# v0_3_1.net
KiCad netlist of a schematic drawn in EAGLE
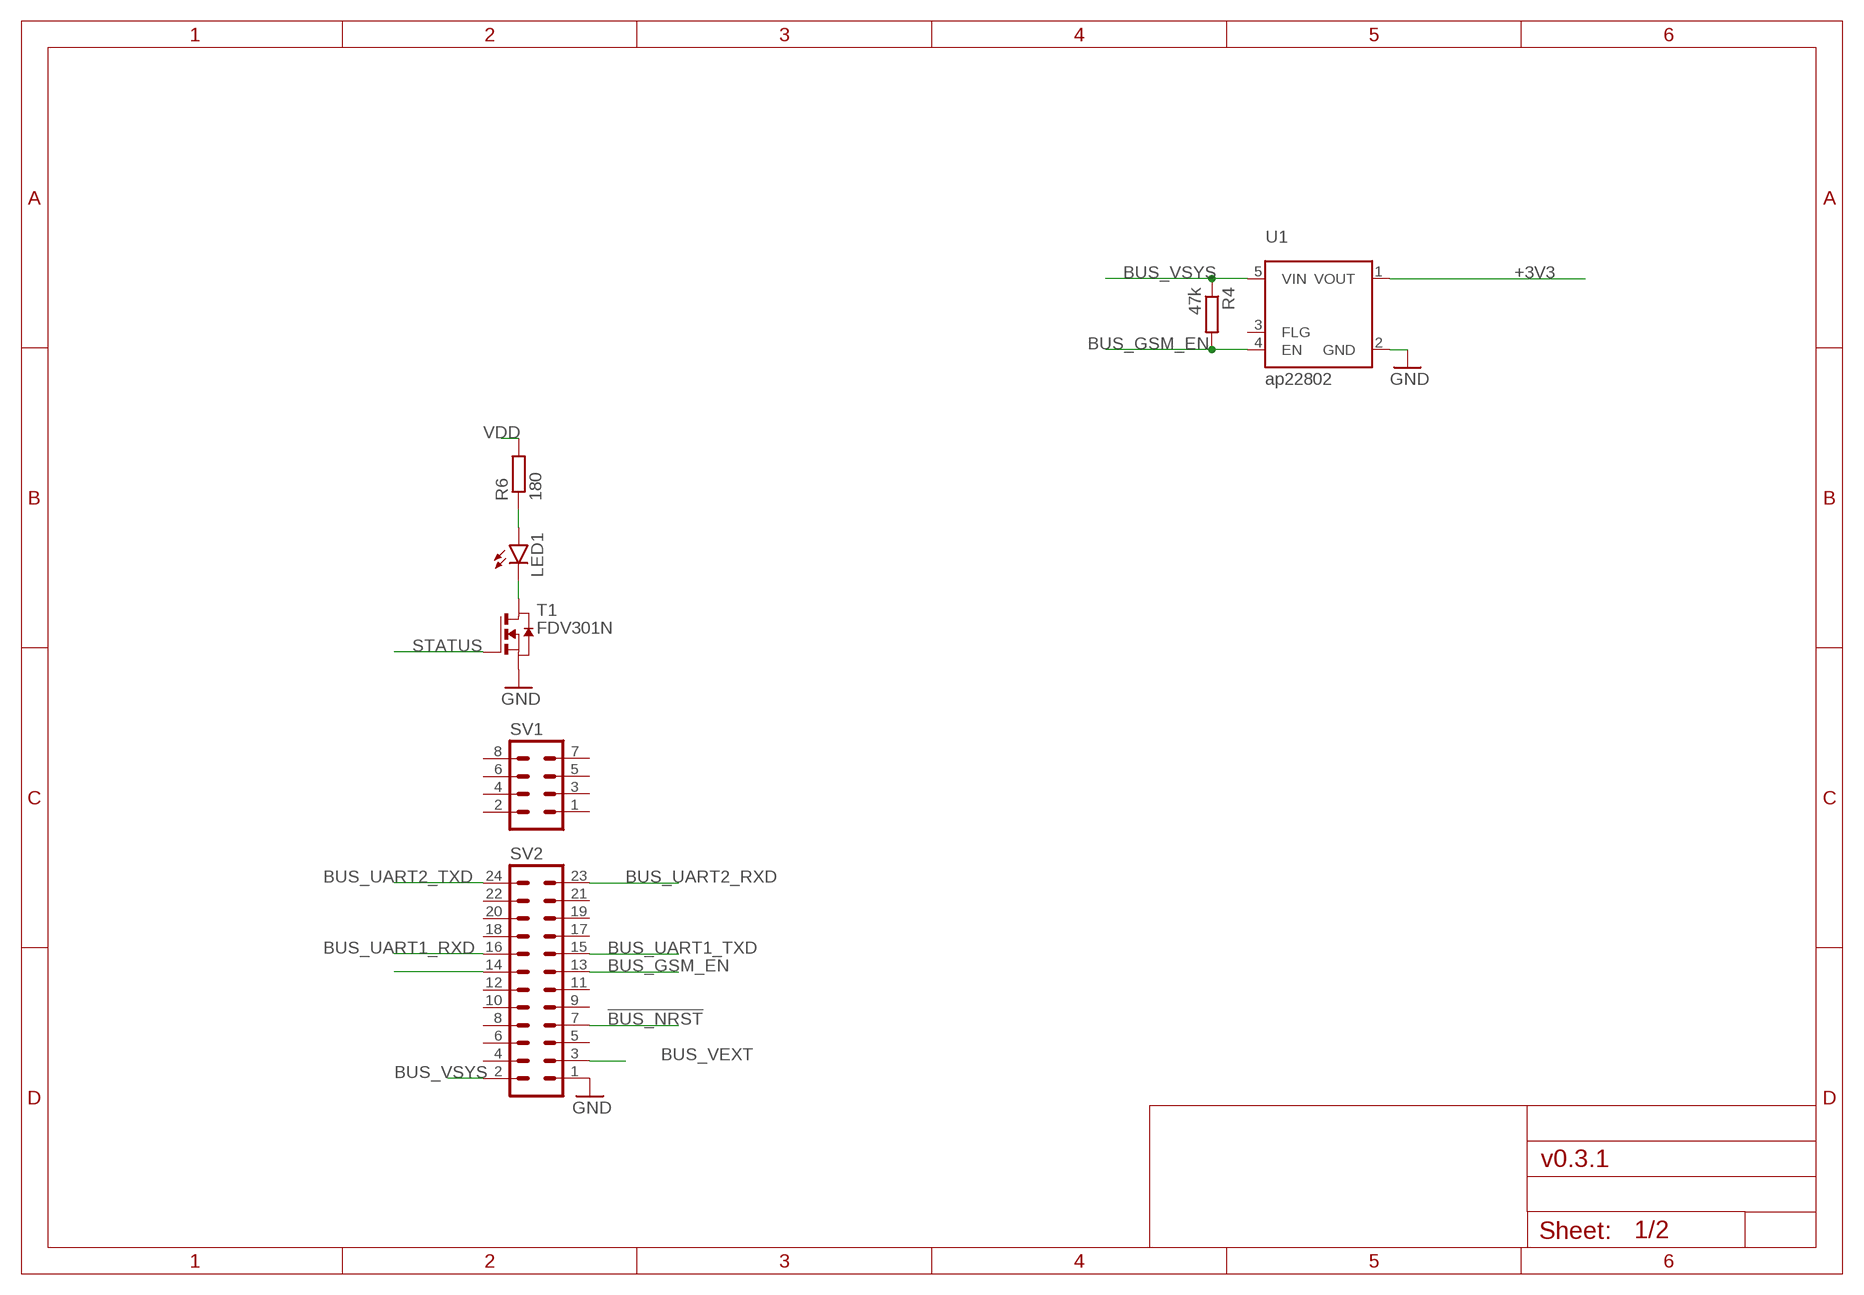
[diagram p0: schematic, sheet 1]
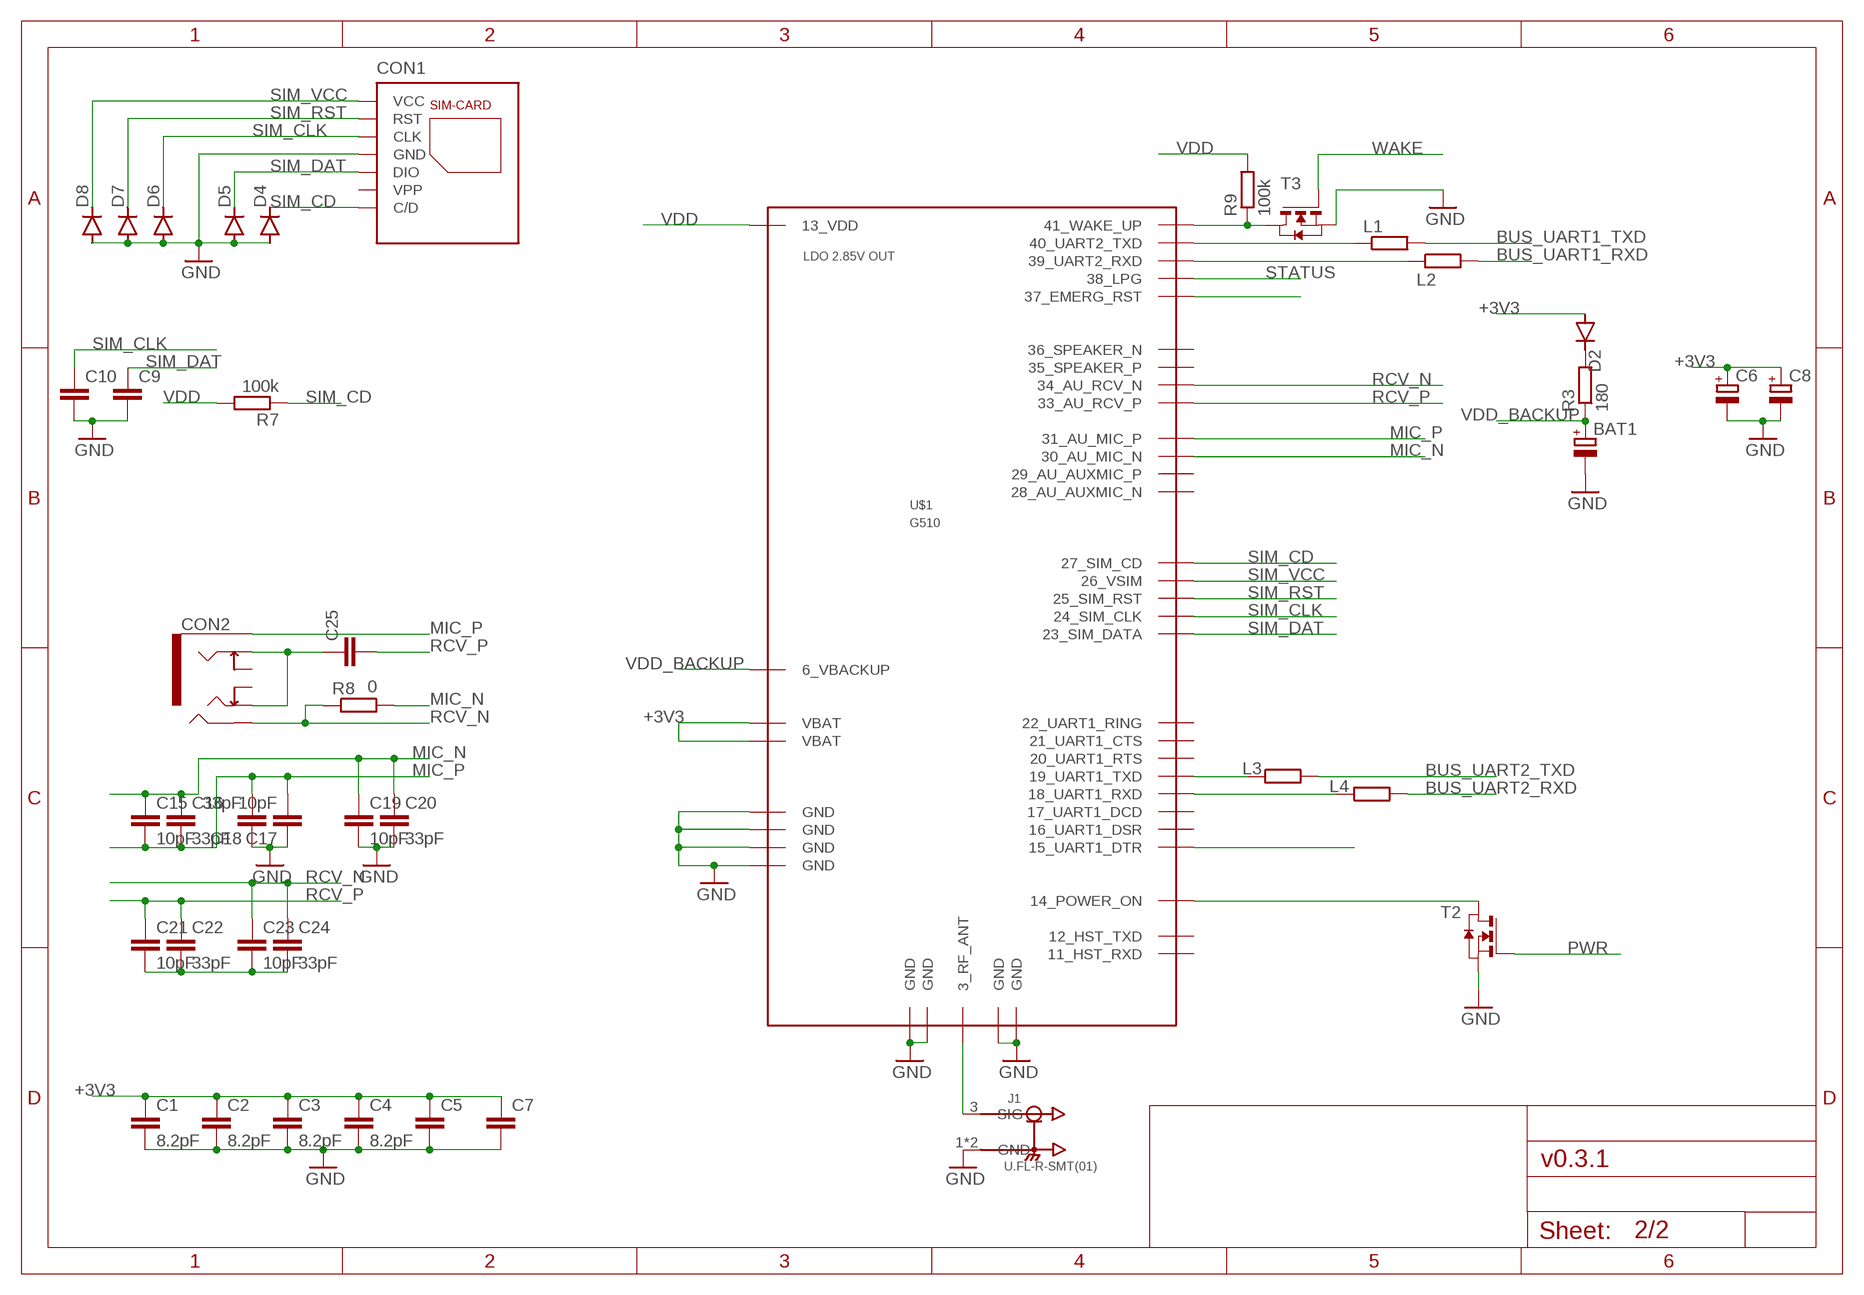
[diagram p1: schematic, sheet 2]

(export (version "E")
  (design (tool "Eeschema 10.0.6"))
  (components
    (comp (ref "LED1")
      (value "LEDCHIP-LED0603")
      (footprint "eagle-import:CHIP-LED0603")
      (libsource (lib "eagle-import") (part "LEDCHIP-LED0603"))
    )
    (comp (ref "R4")
      (value "47k")
      (footprint "eagle-import:R0402")
      (libsource (lib "eagle-import") (part "R-EU_R0402"))
    )
    (comp (ref "R6")
      (value "180")
      (footprint "eagle-import:R0402")
      (libsource (lib "eagle-import") (part "R-EU_R0402"))
    )
    (comp (ref "SV1")
      (value "MA04-2")
      (footprint "eagle-import:MA04-2")
      (libsource (lib "eagle-import") (part "MA04-2"))
    )
    (comp (ref "SV2")
      (value "MA12-2")
      (footprint "eagle-import:MA12-2")
      (libsource (lib "eagle-import") (part "MA12-2"))
    )
    (comp (ref "T1")
      (value "FDV301N")
      (footprint "eagle-import:SOT-23")
      (libsource (lib "eagle-import") (part "NMOSSOT23"))
    )
    (comp (ref "U1")
      (value "ap22802")
      (footprint "eagle-import:SOT25")
      (libsource (lib "eagle-import") (part "AP22802"))
    )
    (comp (ref "BAT1")
      (value "DCK-3R3E224U-E")
      (footprint "eagle-import:621")
      (libsource (lib "eagle-import") (part "DCK-3R3E224U-E"))
    )
    (comp (ref "C1")
      (value "8.2pF")
      (footprint "eagle-import:C0402")
      (libsource (lib "eagle-import") (part "C-EUC0402"))
    )
    (comp (ref "C2")
      (value "8.2pF")
      (footprint "eagle-import:C0402")
      (libsource (lib "eagle-import") (part "C-EUC0402"))
    )
    (comp (ref "C3")
      (value "8.2pF")
      (footprint "eagle-import:C0402")
      (libsource (lib "eagle-import") (part "C-EUC0402"))
    )
    (comp (ref "C4")
      (value "8.2pF")
      (footprint "eagle-import:C0402")
      (libsource (lib "eagle-import") (part "C-EUC0402"))
    )
    (comp (ref "C5")
      (value "C-EUC0603")
      (footprint "eagle-import:C0603")
      (libsource (lib "eagle-import") (part "C-EUC0603"))
    )
    (comp (ref "C6")
      (value "CPOL-EUSMCC")
      (footprint "eagle-import:SMC_C")
      (libsource (lib "eagle-import") (part "CPOL-EUSMCC"))
    )
    (comp (ref "C7")
      (value "C-EUC0603")
      (footprint "eagle-import:C0603")
      (libsource (lib "eagle-import") (part "C-EUC0603"))
    )
    (comp (ref "C8")
      (value "CPOL-EUSMCC")
      (footprint "eagle-import:SMC_C")
      (libsource (lib "eagle-import") (part "CPOL-EUSMCC"))
    )
    (comp (ref "C9")
      (value "C-EUC0402")
      (footprint "eagle-import:C0402")
      (libsource (lib "eagle-import") (part "C-EUC0402"))
    )
    (comp (ref "C10")
      (value "C-EUC0402")
      (footprint "eagle-import:C0402")
      (libsource (lib "eagle-import") (part "C-EUC0402"))
    )
    (comp (ref "C15")
      (value "10pF")
      (footprint "eagle-import:C0402")
      (libsource (lib "eagle-import") (part "C-EUC0402"))
    )
    (comp (ref "C16")
      (value "33pF")
      (footprint "eagle-import:C0402")
      (libsource (lib "eagle-import") (part "C-EUC0402"))
    )
    (comp (ref "C17")
      (value "10pF")
      (footprint "eagle-import:C0402")
      (libsource (lib "eagle-import") (part "C-EUC0402"))
    )
    (comp (ref "C18")
      (value "33pF")
      (footprint "eagle-import:C0402")
      (libsource (lib "eagle-import") (part "C-EUC0402"))
    )
    (comp (ref "C19")
      (value "10pF")
      (footprint "eagle-import:C0402")
      (libsource (lib "eagle-import") (part "C-EUC0402"))
    )
    (comp (ref "C20")
      (value "33pF")
      (footprint "eagle-import:C0402")
      (libsource (lib "eagle-import") (part "C-EUC0402"))
    )
    (comp (ref "C21")
      (value "10pF")
      (footprint "eagle-import:C0402")
      (libsource (lib "eagle-import") (part "C-EUC0402"))
    )
    (comp (ref "C22")
      (value "33pF")
      (footprint "eagle-import:C0402")
      (libsource (lib "eagle-import") (part "C-EUC0402"))
    )
    (comp (ref "C23")
      (value "10pF")
      (footprint "eagle-import:C0402")
      (libsource (lib "eagle-import") (part "C-EUC0402"))
    )
    (comp (ref "C24")
      (value "33pF")
      (footprint "eagle-import:C0402")
      (libsource (lib "eagle-import") (part "C-EUC0402"))
    )
    (comp (ref "C25")
      (value "C-EUC0603")
      (footprint "eagle-import:C0603")
      (libsource (lib "eagle-import") (part "C-EUC0603"))
    )
    (comp (ref "CON1")
      (value "115Q-BCA0")
      (footprint "eagle-import:115Q")
      (libsource (lib "eagle-import") (part "115Q-BCA0"))
    )
    (comp (ref "CON2")
      (value "1503-21")
      (footprint "eagle-import:150321")
      (libsource (lib "eagle-import") (part "1503-21"))
    )
    (comp (ref "D2")
      (value "DIODE-SOD323-R")
      (footprint "eagle-import:SOD323-R")
      (libsource (lib "eagle-import") (part "DIODE-SOD323-R"))
    )
    (comp (ref "D4")
      (value "DIODE-SOD323-R")
      (footprint "eagle-import:SOD323-R")
      (libsource (lib "eagle-import") (part "DIODE-SOD323-R"))
    )
    (comp (ref "D5")
      (value "DIODE-SOD323-R")
      (footprint "eagle-import:SOD323-R")
      (libsource (lib "eagle-import") (part "DIODE-SOD323-R"))
    )
    (comp (ref "D6")
      (value "DIODE-SOD323-R")
      (footprint "eagle-import:SOD323-R")
      (libsource (lib "eagle-import") (part "DIODE-SOD323-R"))
    )
    (comp (ref "D7")
      (value "DIODE-SOD323-R")
      (footprint "eagle-import:SOD323-R")
      (libsource (lib "eagle-import") (part "DIODE-SOD323-R"))
    )
    (comp (ref "D8")
      (value "DIODE-SOD323-R")
      (footprint "eagle-import:SOD323-R")
      (libsource (lib "eagle-import") (part "DIODE-SOD323-R"))
    )
    (comp (ref "J1")
      (value "U.FL-R-SMT(01)")
      (footprint "eagle-import:HRS_U.FL-R-SMT(01)")
      (fields (field (name "MF") "Hirose") (field (name "MP") "U.FL-R-SMT_01_"))
      (libsource (lib "eagle-import") (part "U.FL-R-SMT(01)"))
    )
    (comp (ref "L1")
      (value "R-EU_R0402")
      (footprint "eagle-import:R0402")
      (libsource (lib "eagle-import") (part "R-EU_R0402"))
    )
    (comp (ref "L2")
      (value "R-EU_R0402")
      (footprint "eagle-import:R0402")
      (libsource (lib "eagle-import") (part "R-EU_R0402"))
    )
    (comp (ref "L3")
      (value "R-EU_R0402")
      (footprint "eagle-import:R0402")
      (libsource (lib "eagle-import") (part "R-EU_R0402"))
    )
    (comp (ref "L4")
      (value "R-EU_R0402")
      (footprint "eagle-import:R0402")
      (libsource (lib "eagle-import") (part "R-EU_R0402"))
    )
    (comp (ref "R3")
      (value "180")
      (footprint "eagle-import:R0402")
      (libsource (lib "eagle-import") (part "R-EU_R0402"))
    )
    (comp (ref "R7")
      (value "100k")
      (footprint "eagle-import:R0402")
      (libsource (lib "eagle-import") (part "R-EU_R0402"))
    )
    (comp (ref "R8")
      (value "0")
      (footprint "eagle-import:R0402")
      (libsource (lib "eagle-import") (part "R-EU_R0402"))
    )
    (comp (ref "R9")
      (value "100k")
      (footprint "eagle-import:R0402")
      (libsource (lib "eagle-import") (part "R-EU_R0402"))
    )
    (comp (ref "T2")
      (value "NMOSSOT23")
      (footprint "eagle-import:SOT-23")
      (libsource (lib "eagle-import") (part "NMOSSOT23"))
    )
    (comp (ref "T3")
      (value "NMOSSOT23")
      (footprint "eagle-import:SOT-23")
      (libsource (lib "eagle-import") (part "NMOSSOT23"))
    )
    (comp (ref "U$1")
      (value "G510")
      (footprint "eagle-import:G510")
      (libsource (lib "eagle-import") (part "G510"))
    )
  )
  (nets
    (net (code "1") (name "+3V3") (class "Default")
      (node (ref "C1") (pin "1") (pinfunction "1_1") (pintype "passive"))
      (node (ref "C2") (pin "1") (pinfunction "1_1") (pintype "passive"))
      (node (ref "C3") (pin "1") (pinfunction "1_1") (pintype "passive"))
      (node (ref "C4") (pin "1") (pinfunction "1_1") (pintype "passive"))
      (node (ref "C5") (pin "1") (pinfunction "1_1") (pintype "passive"))
      (node (ref "C6") (pin "+") (pinfunction "+_+") (pintype "passive"))
      (node (ref "C7") (pin "1") (pinfunction "1_1") (pintype "passive"))
      (node (ref "C8") (pin "+") (pinfunction "+_+") (pintype "passive"))
      (node (ref "D2") (pin "A") (pinfunction "A_A") (pintype "passive"))
      (node (ref "U$1") (pin "10_VBAT") (pinfunction "VBAT_10_VBAT") (pintype "power_in"))
      (node (ref "U$1") (pin "9_VBAT") (pinfunction "VBAT_9_VBAT") (pintype "power_in"))
      (node (ref "U1") (pin "1") (pinfunction "VOUT_1") (pintype "bidirectional"))
    )
    (net (code "2") (name "BUS_GSM_EN") (class "Default")
      (node (ref "R4") (pin "2") (pinfunction "2_2") (pintype "passive"))
      (node (ref "SV2") (pin "13") (pinfunction "13_13") (pintype "passive"))
      (node (ref "U1") (pin "4") (pinfunction "EN_4") (pintype "bidirectional"))
    )
    (net (code "3") (name "BUS_UART1_RXD") (class "Default")
      (node (ref "L2") (pin "2") (pinfunction "2_2") (pintype "passive"))
      (node (ref "SV2") (pin "16") (pinfunction "16_16") (pintype "passive"))
    )
    (net (code "4") (name "BUS_UART1_TXD") (class "Default")
      (node (ref "L1") (pin "2") (pinfunction "2_2") (pintype "passive"))
      (node (ref "SV2") (pin "15") (pinfunction "15_15") (pintype "passive"))
    )
    (net (code "5") (name "BUS_UART2_RXD") (class "Default")
      (node (ref "L4") (pin "2") (pinfunction "2_2") (pintype "passive"))
      (node (ref "SV2") (pin "23") (pinfunction "23_23") (pintype "passive"))
    )
    (net (code "6") (name "BUS_UART2_TXD") (class "Default")
      (node (ref "L3") (pin "2") (pinfunction "2_2") (pintype "passive"))
      (node (ref "SV2") (pin "24") (pinfunction "24_24") (pintype "passive"))
    )
    (net (code "7") (name "BUS_VEXT") (class "Default")
      (node (ref "SV2") (pin "3") (pinfunction "3_3") (pintype "passive"))
    )
    (net (code "8") (name "BUS_VSYS") (class "Default")
      (node (ref "R4") (pin "1") (pinfunction "1_1") (pintype "passive"))
      (node (ref "SV2") (pin "2") (pinfunction "2_2") (pintype "passive"))
      (node (ref "U1") (pin "5") (pinfunction "VIN_5") (pintype "bidirectional"))
    )
    (net (code "9") (name "GND") (class "Default")
      (node (ref "BAT1") (pin "-") (pinfunction "-_-") (pintype "passive"))
      (node (ref "C1") (pin "2") (pinfunction "2_2") (pintype "passive"))
      (node (ref "C10") (pin "2") (pinfunction "2_2") (pintype "passive"))
      (node (ref "C17") (pin "1") (pinfunction "1_1") (pintype "passive"))
      (node (ref "C18") (pin "1") (pinfunction "1_1") (pintype "passive"))
      (node (ref "C19") (pin "2") (pinfunction "2_2") (pintype "passive"))
      (node (ref "C2") (pin "2") (pinfunction "2_2") (pintype "passive"))
      (node (ref "C20") (pin "2") (pinfunction "2_2") (pintype "passive"))
      (node (ref "C3") (pin "2") (pinfunction "2_2") (pintype "passive"))
      (node (ref "C4") (pin "2") (pinfunction "2_2") (pintype "passive"))
      (node (ref "C5") (pin "2") (pinfunction "2_2") (pintype "passive"))
      (node (ref "C6") (pin "-") (pinfunction "-_-") (pintype "passive"))
      (node (ref "C7") (pin "2") (pinfunction "2_2") (pintype "passive"))
      (node (ref "C8") (pin "-") (pinfunction "-_-") (pintype "passive"))
      (node (ref "C9") (pin "2") (pinfunction "2_2") (pintype "passive"))
      (node (ref "CON1") (pin "GND1") (pinfunction "GND_GND1") (pintype "passive"))
      (node (ref "CON1") (pin "GND2") (pinfunction "GND_GND2") (pintype "passive"))
      (node (ref "CON1") (pin "GND3") (pinfunction "GND_GND3") (pintype "passive"))
      (node (ref "CON1") (pin "GND4") (pinfunction "GND_GND4") (pintype "passive"))
      (node (ref "CON1") (pin "P5") (pinfunction "GND_P5") (pintype "passive"))
      (node (ref "D4") (pin "A") (pinfunction "A_A") (pintype "passive"))
      (node (ref "D5") (pin "A") (pinfunction "A_A") (pintype "passive"))
      (node (ref "D6") (pin "A") (pinfunction "A_A") (pintype "passive"))
      (node (ref "D7") (pin "A") (pinfunction "A_A") (pintype "passive"))
      (node (ref "D8") (pin "A") (pinfunction "A_A") (pintype "passive"))
      (node (ref "J1") (pin "1") (pinfunction "GND_1") (pintype "passive"))
      (node (ref "J1") (pin "2") (pinfunction "GND_2") (pintype "passive"))
      (node (ref "SV2") (pin "1") (pinfunction "1_1") (pintype "passive"))
      (node (ref "T1") (pin "2") (pinfunction "S_2") (pintype "passive"))
      (node (ref "T2") (pin "2") (pinfunction "S_2") (pintype "passive"))
      (node (ref "T3") (pin "2") (pinfunction "S_2") (pintype "passive"))
      (node (ref "U$1") (pin "1_GND") (pinfunction "GND_1_GND") (pintype "power_in"))
      (node (ref "U$1") (pin "2_GND") (pinfunction "GND_2_GND") (pintype "power_in"))
      (node (ref "U$1") (pin "32_GND") (pinfunction "GND_32_GND") (pintype "power_in"))
      (node (ref "U$1") (pin "42_GND") (pinfunction "GND_42_GND") (pintype "power_in"))
      (node (ref "U$1") (pin "4_GND") (pinfunction "GND_4_GND") (pintype "power_in"))
      (node (ref "U$1") (pin "5_GND") (pinfunction "GND_5_GND") (pintype "power_in"))
      (node (ref "U$1") (pin "7_GND") (pinfunction "GND_7_GND") (pintype "power_in"))
      (node (ref "U$1") (pin "8_GND") (pinfunction "GND_8_GND") (pintype "power_in"))
      (node (ref "U1") (pin "2") (pinfunction "GND_2") (pintype "bidirectional"))
    )
    (net (code "10") (name "MIC_N") (class "Default")
      (node (ref "C15") (pin "1") (pinfunction "1_1") (pintype "passive"))
      (node (ref "C16") (pin "1") (pinfunction "1_1") (pintype "passive"))
      (node (ref "C19") (pin "1") (pinfunction "1_1") (pintype "passive"))
      (node (ref "C20") (pin "1") (pinfunction "1_1") (pintype "passive"))
      (node (ref "R8") (pin "2") (pinfunction "2_2") (pintype "passive"))
      (node (ref "U$1") (pin "30_AU_MIC_N") (pinfunction "30_AU_MIC_N_30_AU_MIC_N") (pintype "bidirectional"))
    )
    (net (code "11") (name "MIC_P") (class "Default")
      (node (ref "C15") (pin "2") (pinfunction "2_2") (pintype "passive"))
      (node (ref "C16") (pin "2") (pinfunction "2_2") (pintype "passive"))
      (node (ref "C17") (pin "2") (pinfunction "2_2") (pintype "passive"))
      (node (ref "C18") (pin "2") (pinfunction "2_2") (pintype "passive"))
      (node (ref "CON2") (pin "1") (pinfunction "1_1") (pintype "bidirectional"))
      (node (ref "U$1") (pin "31_AU_MIC_P") (pinfunction "31_AU_MIC_P_31_AU_MIC_P") (pintype "bidirectional"))
    )
    (net (code "12") (name "Net-(C21-Pad2)") (class "Default")
      (node (ref "C21") (pin "2") (pinfunction "2_2") (pintype "passive"))
      (node (ref "C22") (pin "2") (pinfunction "2_2") (pintype "passive"))
      (node (ref "C23") (pin "2") (pinfunction "2_2") (pintype "passive"))
      (node (ref "C24") (pin "2") (pinfunction "2_2") (pintype "passive"))
    )
    (net (code "13") (name "Net-(C25-Pad1)") (class "Default")
      (node (ref "C25") (pin "1") (pinfunction "1_1") (pintype "passive"))
      (node (ref "CON2") (pin "3") (pinfunction "3_3") (pintype "bidirectional"))
      (node (ref "CON2") (pin "5") (pinfunction "5_5") (pintype "bidirectional"))
    )
    (net (code "14") (name "Net-(D2-PadC)") (class "Default")
      (node (ref "D2") (pin "C") (pinfunction "C_C") (pintype "passive"))
      (node (ref "R3") (pin "2") (pinfunction "2_2") (pintype "passive"))
    )
    (net (code "15") (name "Net-(J1-SIG)") (class "Default")
      (node (ref "J1") (pin "3") (pinfunction "SIG_3") (pintype "passive"))
      (node (ref "U$1") (pin "3_RF_ANT") (pinfunction "3_RF_ANT_3_RF_ANT") (pintype "bidirectional"))
    )
    (net (code "16") (name "Net-(L1-Pad1)") (class "Default")
      (node (ref "L1") (pin "1") (pinfunction "1_1") (pintype "passive"))
      (node (ref "U$1") (pin "40_UART2_TXD") (pinfunction "40_UART2_TXD_40_UART2_TXD") (pintype "output"))
    )
    (net (code "17") (name "Net-(L2-Pad1)") (class "Default")
      (node (ref "L2") (pin "1") (pinfunction "1_1") (pintype "passive"))
      (node (ref "U$1") (pin "39_UART2_RXD") (pinfunction "39_UART2_RXD_39_UART2_RXD") (pintype "input"))
    )
    (net (code "18") (name "Net-(L3-Pad1)") (class "Default")
      (node (ref "L3") (pin "1") (pinfunction "1_1") (pintype "passive"))
      (node (ref "U$1") (pin "19_UART1_TXD") (pinfunction "19_UART1_TXD_19_UART1_TXD") (pintype "output"))
    )
    (net (code "19") (name "Net-(L4-Pad1)") (class "Default")
      (node (ref "L4") (pin "1") (pinfunction "1_1") (pintype "passive"))
      (node (ref "U$1") (pin "18_UART1_RXD") (pinfunction "18_UART1_RXD_18_UART1_RXD") (pintype "input"))
    )
    (net (code "20") (name "Net-(LED1-PadA)") (class "Default")
      (node (ref "LED1") (pin "A") (pinfunction "A_A") (pintype "passive"))
      (node (ref "R6") (pin "1") (pinfunction "1_1") (pintype "passive"))
    )
    (net (code "21") (name "Net-(T1-D)") (class "Default")
      (node (ref "LED1") (pin "C") (pinfunction "C_C") (pintype "passive"))
      (node (ref "T1") (pin "1") (pinfunction "D_1") (pintype "passive"))
    )
    (net (code "22") (name "Net-(T2-D)") (class "Default")
      (node (ref "T2") (pin "1") (pinfunction "D_1") (pintype "passive"))
      (node (ref "U$1") (pin "14_POWER_ON") (pinfunction "14_POWER_ON_14_POWER_ON") (pintype "input"))
    )
    (net (code "23") (name "Net-(T3-D)") (class "Default")
      (node (ref "R9") (pin "1") (pinfunction "1_1") (pintype "passive"))
      (node (ref "T3") (pin "1") (pinfunction "D_1") (pintype "passive"))
      (node (ref "U$1") (pin "41_WAKE_UP") (pinfunction "41_WAKE_UP_41_WAKE_UP") (pintype "bidirectional"))
    )
    (net (code "24") (name "PWR") (class "Default")
      (node (ref "T2") (pin "3") (pinfunction "G_3") (pintype "passive"))
    )
    (net (code "25") (name "RCV_N") (class "Default")
      (node (ref "C23") (pin "1") (pinfunction "1_1") (pintype "passive"))
      (node (ref "C24") (pin "1") (pinfunction "1_1") (pintype "passive"))
      (node (ref "CON2") (pin "2") (pinfunction "2_2") (pintype "bidirectional"))
      (node (ref "R8") (pin "1") (pinfunction "1_1") (pintype "passive"))
      (node (ref "U$1") (pin "34_AU_RCV_N") (pinfunction "34_AU_RCV_N_34_AU_RCV_N") (pintype "bidirectional"))
    )
    (net (code "26") (name "RCV_P") (class "Default")
      (node (ref "C21") (pin "1") (pinfunction "1_1") (pintype "passive"))
      (node (ref "C22") (pin "1") (pinfunction "1_1") (pintype "passive"))
      (node (ref "C25") (pin "2") (pinfunction "2_2") (pintype "passive"))
      (node (ref "U$1") (pin "33_AU_RCV_P") (pinfunction "33_AU_RCV_P_33_AU_RCV_P") (pintype "bidirectional"))
    )
    (net (code "27") (name "SIM_CD") (class "Default")
      (node (ref "CON1") (pin "CD") (pinfunction "C/D_CD") (pintype "passive"))
      (node (ref "D4") (pin "C") (pinfunction "C_C") (pintype "passive"))
      (node (ref "R7") (pin "1") (pinfunction "1_1") (pintype "passive"))
      (node (ref "U$1") (pin "27_SIM_CD") (pinfunction "27_SIM_CD_27_SIM_CD") (pintype "bidirectional"))
    )
    (net (code "28") (name "SIM_CLK") (class "Default")
      (node (ref "C10") (pin "1") (pinfunction "1_1") (pintype "passive"))
      (node (ref "CON1") (pin "P3") (pinfunction "CLK_P3") (pintype "passive"))
      (node (ref "D6") (pin "C") (pinfunction "C_C") (pintype "passive"))
      (node (ref "U$1") (pin "24_SIM_CLK") (pinfunction "24_SIM_CLK_24_SIM_CLK") (pintype "bidirectional"))
    )
    (net (code "29") (name "SIM_DAT") (class "Default")
      (node (ref "C9") (pin "1") (pinfunction "1_1") (pintype "passive"))
      (node (ref "CON1") (pin "P7") (pinfunction "DIO_P7") (pintype "passive"))
      (node (ref "D5") (pin "C") (pinfunction "C_C") (pintype "passive"))
      (node (ref "U$1") (pin "23_SIM_DATA") (pinfunction "23_SIM_DATA_23_SIM_DATA") (pintype "bidirectional"))
    )
    (net (code "30") (name "SIM_RST") (class "Default")
      (node (ref "CON1") (pin "P2") (pinfunction "RST_P2") (pintype "passive"))
      (node (ref "D7") (pin "C") (pinfunction "C_C") (pintype "passive"))
      (node (ref "U$1") (pin "25_SIM_RST") (pinfunction "25_SIM_RST_25_SIM_RST") (pintype "bidirectional"))
    )
    (net (code "31") (name "SIM_VCC") (class "Default")
      (node (ref "CON1") (pin "P1") (pinfunction "VCC_P1") (pintype "passive"))
      (node (ref "D8") (pin "C") (pinfunction "C_C") (pintype "passive"))
      (node (ref "U$1") (pin "26_VSIM") (pinfunction "26_VSIM_26_VSIM") (pintype "bidirectional"))
    )
    (net (code "32") (name "STATUS") (class "Default")
      (node (ref "T1") (pin "3") (pinfunction "G_3") (pintype "passive"))
      (node (ref "U$1") (pin "38_LPG") (pinfunction "38_LPG_38_LPG") (pintype "output"))
    )
    (net (code "33") (name "VDD") (class "Default")
      (node (ref "R6") (pin "2") (pinfunction "2_2") (pintype "passive"))
      (node (ref "R7") (pin "2") (pinfunction "2_2") (pintype "passive"))
      (node (ref "R9") (pin "2") (pinfunction "2_2") (pintype "passive"))
      (node (ref "U$1") (pin "13_VDD") (pinfunction "13_VDD_13_VDD") (pintype "power_in"))
    )
    (net (code "34") (name "VDD_BACKUP") (class "Default")
      (node (ref "BAT1") (pin "+") (pinfunction "+_+") (pintype "passive"))
      (node (ref "R3") (pin "1") (pinfunction "1_1") (pintype "passive"))
      (node (ref "U$1") (pin "6_VBACKUP") (pinfunction "6_VBACKUP_6_VBACKUP") (pintype "power_in"))
    )
    (net (code "35") (name "WAKE") (class "Default")
      (node (ref "T3") (pin "3") (pinfunction "G_3") (pintype "passive"))
    )
    (net (code "36") (name "unconnected-(CON1-VPP-PadP6)") (class "Default")
      (node (ref "CON1") (pin "P6") (pinfunction "VPP_P6") (pintype "passive"))
    )
    (net (code "37") (name "unconnected-(CON2-Pad4)") (class "Default")
      (node (ref "CON2") (pin "4") (pinfunction "4_4") (pintype "bidirectional"))
    )
    (net (code "38") (name "unconnected-(CON2-Pad6)") (class "Default")
      (node (ref "CON2") (pin "6") (pinfunction "6_6") (pintype "bidirectional"))
    )
    (net (code "39") (name "unconnected-(SV1-Pad1)") (class "Default")
      (node (ref "SV1") (pin "1") (pinfunction "1_1") (pintype "passive"))
    )
    (net (code "40") (name "unconnected-(SV1-Pad2)") (class "Default")
      (node (ref "SV1") (pin "2") (pinfunction "2_2") (pintype "passive"))
    )
    (net (code "41") (name "unconnected-(SV1-Pad3)") (class "Default")
      (node (ref "SV1") (pin "3") (pinfunction "3_3") (pintype "passive"))
    )
    (net (code "42") (name "unconnected-(SV1-Pad4)") (class "Default")
      (node (ref "SV1") (pin "4") (pinfunction "4_4") (pintype "passive"))
    )
    (net (code "43") (name "unconnected-(SV1-Pad5)") (class "Default")
      (node (ref "SV1") (pin "5") (pinfunction "5_5") (pintype "passive"))
    )
    (net (code "44") (name "unconnected-(SV1-Pad6)") (class "Default")
      (node (ref "SV1") (pin "6") (pinfunction "6_6") (pintype "passive"))
    )
    (net (code "45") (name "unconnected-(SV1-Pad7)") (class "Default")
      (node (ref "SV1") (pin "7") (pinfunction "7_7") (pintype "passive"))
    )
    (net (code "46") (name "unconnected-(SV1-Pad8)") (class "Default")
      (node (ref "SV1") (pin "8") (pinfunction "8_8") (pintype "passive"))
    )
    (net (code "47") (name "unconnected-(SV2-Pad4)") (class "Default")
      (node (ref "SV2") (pin "4") (pinfunction "4_4") (pintype "passive"))
    )
    (net (code "48") (name "unconnected-(SV2-Pad5)") (class "Default")
      (node (ref "SV2") (pin "5") (pinfunction "5_5") (pintype "passive"))
    )
    (net (code "49") (name "unconnected-(SV2-Pad6)") (class "Default")
      (node (ref "SV2") (pin "6") (pinfunction "6_6") (pintype "passive"))
    )
    (net (code "50") (name "unconnected-(SV2-Pad8)") (class "Default")
      (node (ref "SV2") (pin "8") (pinfunction "8_8") (pintype "passive"))
    )
    (net (code "51") (name "unconnected-(SV2-Pad9)") (class "Default")
      (node (ref "SV2") (pin "9") (pinfunction "9_9") (pintype "passive"))
    )
    (net (code "52") (name "unconnected-(SV2-Pad10)") (class "Default")
      (node (ref "SV2") (pin "10") (pinfunction "10_10") (pintype "passive"))
    )
    (net (code "53") (name "unconnected-(SV2-Pad11)") (class "Default")
      (node (ref "SV2") (pin "11") (pinfunction "11_11") (pintype "passive"))
    )
    (net (code "54") (name "unconnected-(SV2-Pad12)") (class "Default")
      (node (ref "SV2") (pin "12") (pinfunction "12_12") (pintype "passive"))
    )
    (net (code "55") (name "unconnected-(SV2-Pad14)") (class "Default")
      (node (ref "SV2") (pin "14") (pinfunction "14_14") (pintype "passive"))
    )
    (net (code "56") (name "unconnected-(SV2-Pad17)") (class "Default")
      (node (ref "SV2") (pin "17") (pinfunction "17_17") (pintype "passive"))
    )
    (net (code "57") (name "unconnected-(SV2-Pad18)") (class "Default")
      (node (ref "SV2") (pin "18") (pinfunction "18_18") (pintype "passive"))
    )
    (net (code "58") (name "unconnected-(SV2-Pad19)") (class "Default")
      (node (ref "SV2") (pin "19") (pinfunction "19_19") (pintype "passive"))
    )
    (net (code "59") (name "unconnected-(SV2-Pad20)") (class "Default")
      (node (ref "SV2") (pin "20") (pinfunction "20_20") (pintype "passive"))
    )
    (net (code "60") (name "unconnected-(SV2-Pad21)") (class "Default")
      (node (ref "SV2") (pin "21") (pinfunction "21_21") (pintype "passive"))
    )
    (net (code "61") (name "unconnected-(SV2-Pad22)") (class "Default")
      (node (ref "SV2") (pin "22") (pinfunction "22_22") (pintype "passive"))
    )
    (net (code "62") (name "unconnected-(U$1-11_HST_RXD-Pad11_HSTRXD)") (class "Default")
      (node (ref "U$1") (pin "11_HSTRXD") (pinfunction "11_HST_RXD_11_HSTRXD") (pintype "input"))
    )
    (net (code "63") (name "unconnected-(U$1-Pad12_HST_TXD)") (class "Default")
      (node (ref "U$1") (pin "12_HST_TXD") (pinfunction "12_HST_TXD_12_HST_TXD") (pintype "output"))
    )
    (net (code "64") (name "unconnected-(U$1-Pad15_UART1_DTR)") (class "Default")
      (node (ref "U$1") (pin "15_UART1_DTR") (pinfunction "15_UART1_DTR_15_UART1_DTR") (pintype "bidirectional"))
    )
    (net (code "65") (name "unconnected-(U$1-Pad16_UART1_DSR)") (class "Default")
      (node (ref "U$1") (pin "16_UART1_DSR") (pinfunction "16_UART1_DSR_16_UART1_DSR") (pintype "bidirectional"))
    )
    (net (code "66") (name "unconnected-(U$1-Pad17_UART1_DCD)") (class "Default")
      (node (ref "U$1") (pin "17_UART1_DCD") (pinfunction "17_UART1_DCD_17_UART1_DCD") (pintype "bidirectional"))
    )
    (net (code "67") (name "unconnected-(U$1-Pad20_UART1_RTS)") (class "Default")
      (node (ref "U$1") (pin "20_UART1_RTS") (pinfunction "20_UART1_RTS_20_UART1_RTS") (pintype "bidirectional"))
    )
    (net (code "68") (name "unconnected-(U$1-Pad21_UART1_CTS)") (class "Default")
      (node (ref "U$1") (pin "21_UART1_CTS") (pinfunction "21_UART1_CTS_21_UART1_CTS") (pintype "bidirectional"))
    )
    (net (code "69") (name "unconnected-(U$1-Pad22_UART1_RING)") (class "Default")
      (node (ref "U$1") (pin "22_UART1_RING") (pinfunction "22_UART1_RING_22_UART1_RING") (pintype "bidirectional"))
    )
    (net (code "70") (name "unconnected-(U$1-Pad28_AU_AUXMIC_N)") (class "Default")
      (node (ref "U$1") (pin "28_AU_AUXMIC_N") (pinfunction "28_AU_AUXMIC_N_28_AU_AUXMIC_N") (pintype "bidirectional"))
    )
    (net (code "71") (name "unconnected-(U$1-Pad29_AU_AUXMIC_P)") (class "Default")
      (node (ref "U$1") (pin "29_AU_AUXMIC_P") (pinfunction "29_AU_AUXMIC_P_29_AU_AUXMIC_P") (pintype "bidirectional"))
    )
    (net (code "72") (name "unconnected-(U$1-Pad35_SPEAKER_P)") (class "Default")
      (node (ref "U$1") (pin "35_SPEAKER_P") (pinfunction "35_SPEAKER_P_35_SPEAKER_P") (pintype "bidirectional"))
    )
    (net (code "73") (name "unconnected-(U$1-Pad36_SPEAKER_N)") (class "Default")
      (node (ref "U$1") (pin "36_SPEAKER_N") (pinfunction "36_SPEAKER_N_36_SPEAKER_N") (pintype "bidirectional"))
    )
    (net (code "74") (name "unconnected-(U$1-Pad37_EMERG_RST)") (class "Default")
      (node (ref "U$1") (pin "37_EMERG_RST") (pinfunction "37_EMERG_RST_37_EMERG_RST") (pintype "input"))
    )
    (net (code "75") (name "unconnected-(U1-FLG-Pad3)") (class "Default")
      (node (ref "U1") (pin "3") (pinfunction "FLG_3") (pintype "bidirectional"))
    )
    (net (code "76") (name "~{BUS_NRST}") (class "Default")
      (node (ref "SV2") (pin "7") (pinfunction "7_7") (pintype "passive"))
    )
  )
)
